# S7_WiFi.net
KiCad netlist of a schematic drawn in Altium Designer
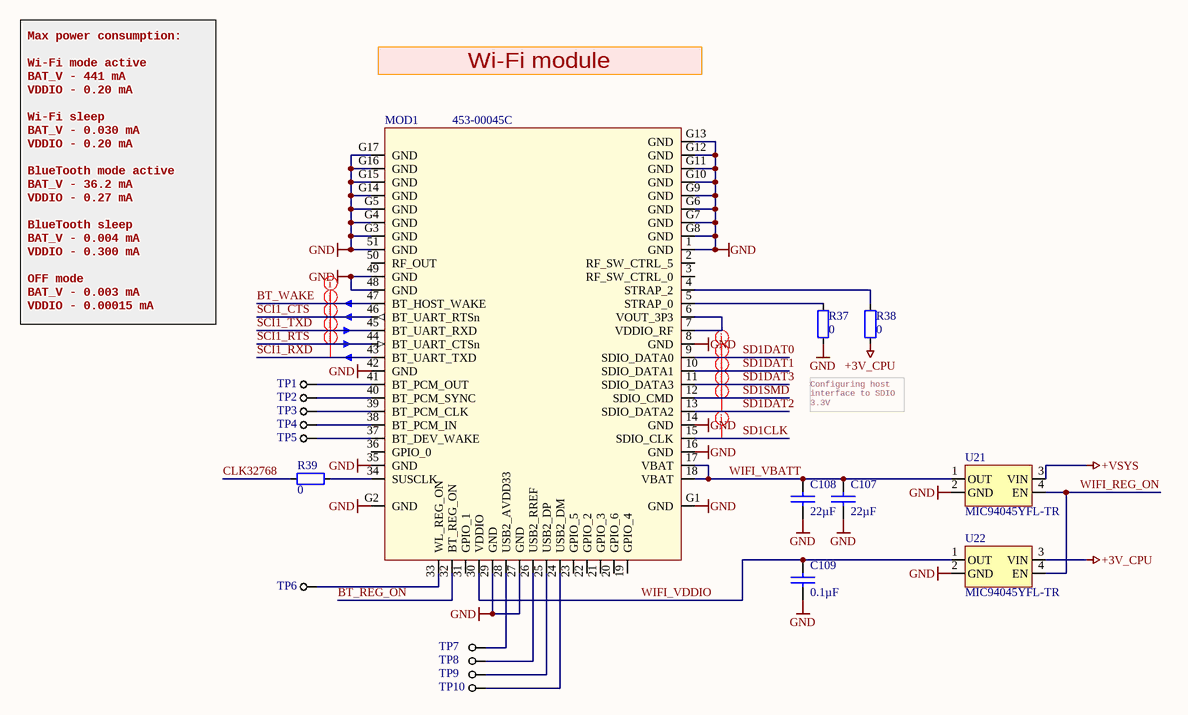
[diagram p0: S7_WiFi.SchDoc]

(export (version "E")
  (design (tool "Eeschema 10.0.6"))
  (components
    (comp (ref "C107")
      (value "22µF")
      (footprint "0603 CAP")
      (description "22µF, ±20%, 10V, X5R, 0603 (1608 Metric), -55°C ~ 85°C, -, SMPS Filtering")
      (fields (field (name "PART NUMBER") "LMK107BBJ226MA-T") (field (name "MANUFACTURER") "Taiyo Yuden"))
      (libsource (lib "ea_PassivComps") (part "Capacitor"))
    )
    (comp (ref "C108")
      (value "22µF")
      (footprint "0603 CAP")
      (description "22µF, ±20%, 10V, X5R, 0603 (1608 Metric), -55°C ~ 85°C, -, SMPS Filtering")
      (fields (field (name "PART NUMBER") "LMK107BBJ226MA-T") (field (name "MANUFACTURER") "Taiyo Yuden"))
      (libsource (lib "ea_PassivComps") (part "Capacitor"))
    )
    (comp (ref "C109")
      (value "0.1µF")
      (footprint "0402 CAP")
      (description "0.1µF, ±10%, 50V, X7R, 0402 (1005 Metric), -55°C ~ 125°C, -, General Purpose")
      (fields
        (field (name "PART NUMBER") "0402B104K500CT")
        (field (name "MANUFACTURER") "Walsin Technology Corporation")
      )
      (libsource (lib "ea_PassivComps") (part "Capacitor"))
    )
    (comp (ref "MOD1")
      (value "453-00045C")
      (footprint "LWB5+ 453-00045C")
      (description "Module, Sterling LWB5+")
      (fields (field (name "MANUFACTURER") "Laird"))
      (libsource (lib "ea_WiFi_modules") (part "CMP-MOD-453-00012-1.4"))
    )
    (comp (ref "R37")
      (value "0")
      (footprint "0402")
      (description "0 Ohms Jumper 0.063W, 1/16W Chip Resistor 0402 (1005 Metric) Thick Film")
      (fields (field (name "MANUFACTURER") "Walsin Technology Corporation") (field (name "VOLTAGE") "50 V"))
      (libsource (lib "ea_Resistors_0402") (part "WR04X000 PTL"))
    )
    (comp (ref "R38")
      (value "0")
      (footprint "0402")
      (description "0 Ohms Jumper 0.063W, 1/16W Chip Resistor 0402 (1005 Metric) Thick Film")
      (fields (field (name "MANUFACTURER") "Walsin Technology Corporation") (field (name "VOLTAGE") "50 V"))
      (libsource (lib "ea_Resistors_0402") (part "WR04X000 PTL"))
    )
    (comp (ref "R39")
      (value "0")
      (footprint "0402")
      (description "0 Ohms Jumper 0.063W, 1/16W Chip Resistor 0402 (1005 Metric) Thick Film")
      (fields (field (name "MANUFACTURER") "Walsin Technology Corporation") (field (name "VOLTAGE") "50 V"))
      (libsource (lib "") (part "WR04X000 PTL_1"))
    )
    (comp (ref "TP1")
      (value "Test_point 0.5 мм")
      (footprint "Test point 0.5 мм")
      (libsource (lib "ea_Contacts") (part "Test_point 0.5 мм"))
    )
    (comp (ref "TP2")
      (value "Test_point 0.5 мм")
      (footprint "Test point 0.5 мм")
      (libsource (lib "ea_Contacts") (part "Test_point 0.5 мм"))
    )
    (comp (ref "TP3")
      (value "Test_point 0.5 мм")
      (footprint "Test point 0.5 мм")
      (libsource (lib "ea_Contacts") (part "Test_point 0.5 мм"))
    )
    (comp (ref "TP4")
      (value "Test_point 0.5 мм")
      (footprint "Test point 0.5 мм")
      (libsource (lib "ea_Contacts") (part "Test_point 0.5 мм"))
    )
    (comp (ref "TP5")
      (value "Test_point 0.5 мм")
      (footprint "Test point 0.5 мм")
      (libsource (lib "ea_Contacts") (part "Test_point 0.5 мм"))
    )
    (comp (ref "TP6")
      (value "Test_point 0.5 мм")
      (footprint "Test point 0.5 мм")
      (libsource (lib "ea_Contacts") (part "Test_point 0.5 мм"))
    )
    (comp (ref "TP7")
      (value "Test_point 0.5 мм")
      (footprint "Test point 0.5 мм")
      (libsource (lib "ea_Contacts") (part "Test_point 0.5 мм"))
    )
    (comp (ref "TP8")
      (value "Test_point 0.5 мм")
      (footprint "Test point 0.5 мм")
      (libsource (lib "ea_Contacts") (part "Test_point 0.5 мм"))
    )
    (comp (ref "TP9")
      (value "Test_point 0.5 мм")
      (footprint "Test point 0.5 мм")
      (libsource (lib "ea_Contacts") (part "Test_point 0.5 мм"))
    )
    (comp (ref "TP10")
      (value "Test_point 0.5 мм")
      (footprint "Test point 0.5 мм")
      (libsource (lib "ea_Contacts") (part "Test_point 0.5 мм"))
    )
    (comp (ref "U21")
      (value "MIC94045YFL-TR")
      (footprint "4-WDFN")
      (description "Power Switch P-Channel, 1.7V ~ 5.5V, 3A, 28 mOhm,   4-MLF® (1.2x1.2), -40...125 C")
      (fields (field (name "MANUFACTURER") "Microchip Technology") (field (name "PARTNUM") "576-3973-1-ND"))
      (libsource (lib "MIC94045") (part "MIC94045YFL-TR"))
    )
    (comp (ref "U22")
      (value "MIC94045YFL-TR")
      (footprint "4-WDFN")
      (description "Power Switch P-Channel, 1.7V ~ 5.5V, 3A, 28 mOhm,   4-MLF® (1.2x1.2), -40...125 C")
      (fields (field (name "MANUFACTURER") "Microchip Technology") (field (name "PARTNUM") "576-3973-1-ND"))
      (libsource (lib "MIC94045") (part "MIC94045YFL-TR"))
    )
  )
  (nets
    (net (code "1") (name "+3V_CPU") (class "Default")
      (node (ref "R38") (pin "1") (pinfunction "1_1") (pintype "passive"))
      (node (ref "U22") (pin "3") (pinfunction "VIN_3") (pintype "passive"))
    )
    (net (code "2") (name "+VSYS") (class "Default")
      (node (ref "U21") (pin "3") (pinfunction "VIN_3") (pintype "passive"))
    )
    (net (code "3") (name "/BT_REG_ON") (class "Default")
      (node (ref "MOD1") (pin "32") (pinfunction "BT_REG_ON_32") (pintype "passive"))
    )
    (net (code "4") (name "/BT_WAKE") (class "Default")
      (node (ref "MOD1") (pin "47") (pinfunction "BT_HOST_WAKE_47") (pintype "passive"))
    )
    (net (code "5") (name "/CLK32768") (class "Default")
      (node (ref "R39") (pin "2") (pinfunction "2_2") (pintype "passive"))
    )
    (net (code "6") (name "/SCI1_CTS") (class "Default")
      (node (ref "MOD1") (pin "46") (pinfunction "BT_UART_RTSn_46") (pintype "output"))
    )
    (net (code "7") (name "/SCI1_RTS") (class "Default")
      (node (ref "MOD1") (pin "44") (pinfunction "BT_UART_CTSn_44") (pintype "input"))
    )
    (net (code "8") (name "/SCI1_RXD") (class "Default")
      (node (ref "MOD1") (pin "43") (pinfunction "BT_UART_TXD_43") (pintype "passive"))
    )
    (net (code "9") (name "/SCI1_TXD") (class "Default")
      (node (ref "MOD1") (pin "45") (pinfunction "BT_UART_RXD_45") (pintype "passive"))
    )
    (net (code "10") (name "/SD1CLK") (class "Default")
      (node (ref "MOD1") (pin "15") (pinfunction "SDIO_CLK_15") (pintype "passive"))
    )
    (net (code "11") (name "/SD1DAT0") (class "Default")
      (node (ref "MOD1") (pin "9") (pinfunction "SDIO_DATA0_9") (pintype "passive"))
    )
    (net (code "12") (name "/SD1DAT1") (class "Default")
      (node (ref "MOD1") (pin "10") (pinfunction "SDIO_DATA1_10") (pintype "passive"))
    )
    (net (code "13") (name "/SD1DAT2") (class "Default")
      (node (ref "MOD1") (pin "13") (pinfunction "SDIO_DATA2_13") (pintype "passive"))
    )
    (net (code "14") (name "/SD1DAT3") (class "Default")
      (node (ref "MOD1") (pin "11") (pinfunction "SDIO_DATA3_11") (pintype "passive"))
    )
    (net (code "15") (name "/SD1SMD") (class "Default")
      (node (ref "MOD1") (pin "12") (pinfunction "SDIO_CMD_12") (pintype "passive"))
    )
    (net (code "16") (name "/WIFI_REG_ON") (class "Default")
      (node (ref "U21") (pin "4") (pinfunction "EN_4") (pintype "passive"))
      (node (ref "U22") (pin "4") (pinfunction "EN_4") (pintype "passive"))
    )
    (net (code "17") (name "/WIFI_VBATT") (class "Default")
      (node (ref "C107") (pin "1") (pinfunction "1_1") (pintype "passive"))
      (node (ref "C108") (pin "1") (pinfunction "1_1") (pintype "passive"))
      (node (ref "MOD1") (pin "17") (pinfunction "VBAT_17") (pintype "passive"))
      (node (ref "MOD1") (pin "18") (pinfunction "VBAT_18") (pintype "passive"))
      (node (ref "U21") (pin "1") (pinfunction "OUT_1") (pintype "passive"))
    )
    (net (code "18") (name "/WIFI_VDDIO") (class "Default")
      (node (ref "C109") (pin "1") (pinfunction "1_1") (pintype "passive"))
      (node (ref "MOD1") (pin "30") (pinfunction "VDDIO_30") (pintype "passive"))
      (node (ref "U22") (pin "1") (pinfunction "OUT_1") (pintype "passive"))
    )
    (net (code "19") (name "GND") (class "Default")
      (node (ref "C107") (pin "2") (pinfunction "2_2") (pintype "passive"))
      (node (ref "C108") (pin "2") (pinfunction "2_2") (pintype "passive"))
      (node (ref "C109") (pin "2") (pinfunction "2_2") (pintype "passive"))
      (node (ref "MOD1") (pin "1") (pinfunction "GND_1") (pintype "passive"))
      (node (ref "MOD1") (pin "14") (pinfunction "GND_14") (pintype "passive"))
      (node (ref "MOD1") (pin "16") (pinfunction "GND_16") (pintype "passive"))
      (node (ref "MOD1") (pin "27") (pinfunction "GND_27") (pintype "passive"))
      (node (ref "MOD1") (pin "29") (pinfunction "GND_29") (pintype "passive"))
      (node (ref "MOD1") (pin "35") (pinfunction "GND_35") (pintype "passive"))
      (node (ref "MOD1") (pin "42") (pinfunction "GND_42") (pintype "passive"))
      (node (ref "MOD1") (pin "48") (pinfunction "GND_48") (pintype "passive"))
      (node (ref "MOD1") (pin "49") (pinfunction "GND_49") (pintype "passive"))
      (node (ref "MOD1") (pin "51") (pinfunction "GND_51") (pintype "passive"))
      (node (ref "MOD1") (pin "8") (pinfunction "GND_8") (pintype "passive"))
      (node (ref "MOD1") (pin "G1") (pinfunction "GND_G1") (pintype "passive"))
      (node (ref "MOD1") (pin "G10") (pinfunction "GND_G10") (pintype "passive"))
      (node (ref "MOD1") (pin "G11") (pinfunction "GND_G11") (pintype "passive"))
      (node (ref "MOD1") (pin "G12") (pinfunction "GND_G12") (pintype "passive"))
      (node (ref "MOD1") (pin "G13") (pinfunction "GND_G13") (pintype "passive"))
      (node (ref "MOD1") (pin "G14") (pinfunction "GND_G14") (pintype "passive"))
      (node (ref "MOD1") (pin "G15") (pinfunction "GND_G15") (pintype "passive"))
      (node (ref "MOD1") (pin "G16") (pinfunction "GND_G16") (pintype "passive"))
      (node (ref "MOD1") (pin "G17") (pinfunction "GND_G17") (pintype "passive"))
      (node (ref "MOD1") (pin "G2") (pinfunction "GND_G2") (pintype "passive"))
      (node (ref "MOD1") (pin "G3") (pinfunction "GND_G3") (pintype "passive"))
      (node (ref "MOD1") (pin "G4") (pinfunction "GND_G4") (pintype "passive"))
      (node (ref "MOD1") (pin "G5") (pinfunction "GND_G5") (pintype "passive"))
      (node (ref "MOD1") (pin "G6") (pinfunction "GND_G6") (pintype "passive"))
      (node (ref "MOD1") (pin "G7") (pinfunction "GND_G7") (pintype "passive"))
      (node (ref "MOD1") (pin "G8") (pinfunction "GND_G8") (pintype "passive"))
      (node (ref "MOD1") (pin "G9") (pinfunction "GND_G9") (pintype "passive"))
      (node (ref "R37") (pin "1") (pinfunction "1_1") (pintype "passive"))
      (node (ref "U21") (pin "2") (pinfunction "GND_2") (pintype "passive"))
      (node (ref "U22") (pin "2") (pinfunction "GND_2") (pintype "passive"))
    )
    (net (code "20") (name "Net-(MOD1-BT_DEV_WAKE)") (class "Default")
      (node (ref "MOD1") (pin "37") (pinfunction "BT_DEV_WAKE_37") (pintype "passive"))
      (node (ref "TP5") (pin "1") (pinfunction "1_1") (pintype "passive"))
    )
    (net (code "21") (name "Net-(MOD1-BT_PCM_CLK)") (class "Default")
      (node (ref "MOD1") (pin "39") (pinfunction "BT_PCM_CLK_39") (pintype "passive"))
      (node (ref "TP3") (pin "1") (pinfunction "1_1") (pintype "passive"))
    )
    (net (code "22") (name "Net-(MOD1-BT_PCM_IN)") (class "Default")
      (node (ref "MOD1") (pin "38") (pinfunction "BT_PCM_IN_38") (pintype "passive"))
      (node (ref "TP4") (pin "1") (pinfunction "1_1") (pintype "passive"))
    )
    (net (code "23") (name "Net-(MOD1-BT_PCM_OUT)") (class "Default")
      (node (ref "MOD1") (pin "41") (pinfunction "BT_PCM_OUT_41") (pintype "passive"))
      (node (ref "TP1") (pin "1") (pinfunction "1_1") (pintype "passive"))
    )
    (net (code "24") (name "Net-(MOD1-BT_PCM_SYNC)") (class "Default")
      (node (ref "MOD1") (pin "40") (pinfunction "BT_PCM_SYNC_40") (pintype "passive"))
      (node (ref "TP2") (pin "1") (pinfunction "1_1") (pintype "passive"))
    )
    (net (code "25") (name "Net-(MOD1-STRAP_0)") (class "Default")
      (node (ref "MOD1") (pin "5") (pinfunction "STRAP_0_5") (pintype "passive"))
      (node (ref "R37") (pin "2") (pinfunction "2_2") (pintype "passive"))
    )
    (net (code "26") (name "Net-(MOD1-STRAP_2)") (class "Default")
      (node (ref "MOD1") (pin "4") (pinfunction "STRAP_2_4") (pintype "passive"))
      (node (ref "R38") (pin "2") (pinfunction "2_2") (pintype "passive"))
    )
    (net (code "27") (name "Net-(MOD1-SUSCLK)") (class "Default")
      (node (ref "MOD1") (pin "34") (pinfunction "SUSCLK_34") (pintype "passive"))
      (node (ref "R39") (pin "1") (pinfunction "1_1") (pintype "passive"))
    )
    (net (code "28") (name "Net-(MOD1-USB2_AVDD33)") (class "Default")
      (node (ref "MOD1") (pin "28") (pinfunction "USB2_AVDD33_28") (pintype "passive"))
      (node (ref "TP7") (pin "1") (pinfunction "1_1") (pintype "passive"))
    )
    (net (code "29") (name "Net-(MOD1-USB2_DM)") (class "Default")
      (node (ref "MOD1") (pin "24") (pinfunction "USB2_DM_24") (pintype "passive"))
      (node (ref "TP10") (pin "1") (pinfunction "1_1") (pintype "passive"))
    )
    (net (code "30") (name "Net-(MOD1-USB2_DP)") (class "Default")
      (node (ref "MOD1") (pin "25") (pinfunction "USB2_DP_25") (pintype "passive"))
      (node (ref "TP9") (pin "1") (pinfunction "1_1") (pintype "passive"))
    )
    (net (code "31") (name "Net-(MOD1-USB2_RREF)") (class "Default")
      (node (ref "MOD1") (pin "26") (pinfunction "USB2_RREF_26") (pintype "passive"))
      (node (ref "TP8") (pin "1") (pinfunction "1_1") (pintype "passive"))
    )
    (net (code "32") (name "Net-(MOD1-VDDIO_RF)") (class "Default")
      (node (ref "MOD1") (pin "6") (pinfunction "VOUT_3P3_6") (pintype "passive"))
      (node (ref "MOD1") (pin "7") (pinfunction "VDDIO_RF_7") (pintype "passive"))
    )
    (net (code "33") (name "Net-(MOD1-WL_REG_ON)") (class "Default")
      (node (ref "MOD1") (pin "33") (pinfunction "WL_REG_ON_33") (pintype "passive"))
      (node (ref "TP6") (pin "1") (pinfunction "1_1") (pintype "passive"))
    )
    (net (code "34") (name "unconnected-(MOD1-GPIO_0-Pad36)") (class "Default")
      (node (ref "MOD1") (pin "36") (pinfunction "GPIO_0_36") (pintype "passive"))
    )
    (net (code "35") (name "unconnected-(MOD1-GPIO_1-Pad31)") (class "Default")
      (node (ref "MOD1") (pin "31") (pinfunction "GPIO_1_31") (pintype "passive"))
    )
    (net (code "36") (name "unconnected-(MOD1-GPIO_2-Pad22)") (class "Default")
      (node (ref "MOD1") (pin "22") (pinfunction "GPIO_2_22") (pintype "passive"))
    )
    (net (code "37") (name "unconnected-(MOD1-GPIO_3-Pad21)") (class "Default")
      (node (ref "MOD1") (pin "21") (pinfunction "GPIO_3_21") (pintype "passive"))
    )
    (net (code "38") (name "unconnected-(MOD1-GPIO_4-Pad19)") (class "Default")
      (node (ref "MOD1") (pin "19") (pinfunction "GPIO_4_19") (pintype "passive"))
    )
    (net (code "39") (name "unconnected-(MOD1-GPIO_5-Pad23)") (class "Default")
      (node (ref "MOD1") (pin "23") (pinfunction "GPIO_5_23") (pintype "passive"))
    )
    (net (code "40") (name "unconnected-(MOD1-GPIO_6-Pad20)") (class "Default")
      (node (ref "MOD1") (pin "20") (pinfunction "GPIO_6_20") (pintype "passive"))
    )
    (net (code "41") (name "unconnected-(MOD1-RF_OUT-Pad50)") (class "Default")
      (node (ref "MOD1") (pin "50") (pinfunction "RF_OUT_50") (pintype "passive"))
    )
    (net (code "42") (name "unconnected-(MOD1-RF_SW_CTRL_0-Pad3)") (class "Default")
      (node (ref "MOD1") (pin "3") (pinfunction "RF_SW_CTRL_0_3") (pintype "passive"))
    )
    (net (code "43") (name "unconnected-(MOD1-RF_SW_CTRL_5-Pad2)") (class "Default")
      (node (ref "MOD1") (pin "2") (pinfunction "RF_SW_CTRL_5_2") (pintype "passive"))
    )
  )
)
